# ComparatorSense.net
KiCad netlist of a schematic drawn in Altium Designer
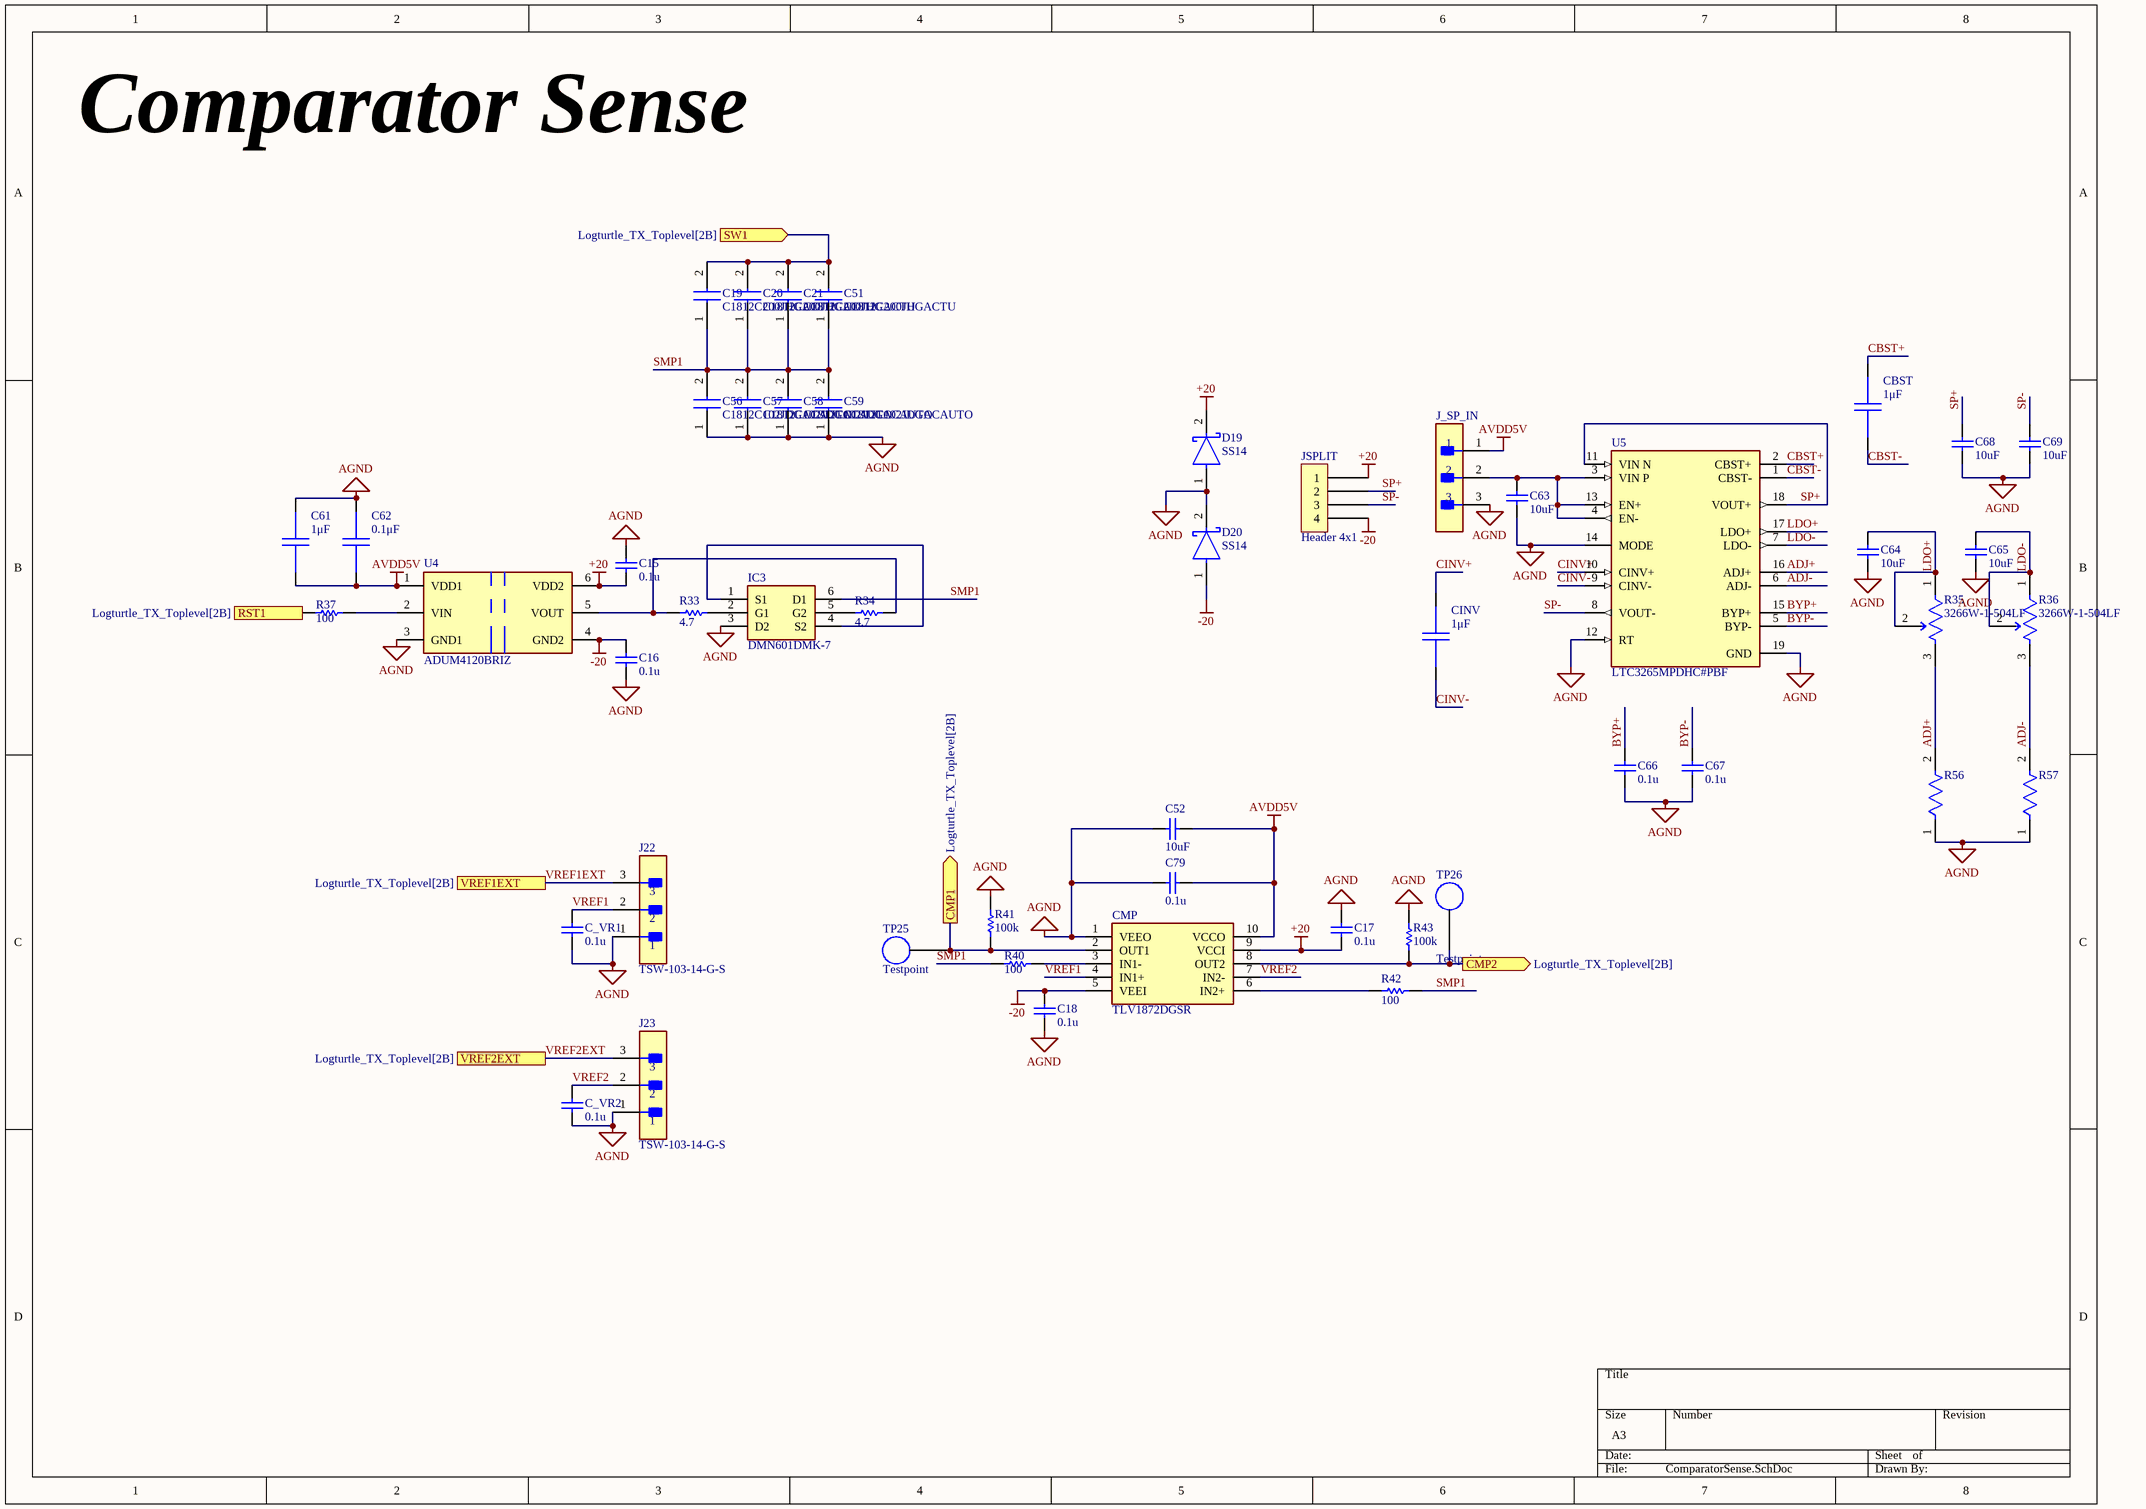
[diagram p0: ComparatorSense.SchDoc]

(export (version "E")
  (design (tool "Eeschema 10.0.6"))
  (components
    (comp (ref "C15")
      (value "0.1u")
      (footprint "CAPC1608X09N")
      (description "Capacitor")
      (libsource (lib "LOGTURTLE_APR_25_TX") (part "Capacitor"))
    )
    (comp (ref "C16")
      (value "0.1u")
      (footprint "CAPC1608X09N")
      (description "Capacitor")
      (libsource (lib "LOGTURTLE_APR_25_TX") (part "Capacitor"))
    )
    (comp (ref "C17")
      (value "0.1u")
      (footprint "CAPC1608X09N")
      (description "Capacitor")
      (libsource (lib "LOGTURTLE_APR_25_TX") (part "Capacitor"))
    )
    (comp (ref "C18")
      (value "0.1u")
      (footprint "CAPC1608X09N")
      (description "Capacitor")
      (libsource (lib "LOGTURTLE_APR_25_TX") (part "Capacitor"))
    )
    (comp (ref "C19")
      (value "C1812C200JHGACTU")
      (footprint "C1812")
      (description "Capacitor")
      (fields (field (name "MANUFACTURER_PART_NUMBER") "C1812C102JDGACAUTO"))
      (libsource (lib "LOGTURTLE_APR_25_TX") (part "C1812C102JDGACAUTO"))
    )
    (comp (ref "C20")
      (value "C1812C200JHGACTU")
      (footprint "C1812")
      (description "Capacitor")
      (fields (field (name "MANUFACTURER_PART_NUMBER") "C1812C102JDGACAUTO"))
      (libsource (lib "LOGTURTLE_APR_25_TX") (part "C1812C102JDGACAUTO"))
    )
    (comp (ref "C21")
      (value "C1812C200JHGACTU")
      (footprint "C1812")
      (description "Capacitor")
      (fields (field (name "MANUFACTURER_PART_NUMBER") "C1812C102JDGACAUTO"))
      (libsource (lib "LOGTURTLE_APR_25_TX") (part "C1812C102JDGACAUTO"))
    )
    (comp (ref "C51")
      (value "C1812C200JHGACTU")
      (footprint "C1812")
      (description "Capacitor")
      (fields (field (name "MANUFACTURER_PART_NUMBER") "C1812C102JDGACAUTO"))
      (libsource (lib "LOGTURTLE_APR_25_TX") (part "C1812C102JDGACAUTO"))
    )
    (comp (ref "C52")
      (value "10uF")
      (footprint "CAPC2012X14N")
      (fields
        (field (name "MANUFACTURER") "Murata")
        (field (name "MANUFACTURER PART NUMBER") "GRM21BZ71E106KE15L")
        (field (name "TOLERANCE") "10%")
      )
      (libsource (lib "LOGTURTLE_APR_25_TX") (part "GRM21BZ71E106KE15L"))
    )
    (comp (ref "C56")
      (value "C1812C102JDGACAUTO")
      (footprint "C1812")
      (description "Capacitor")
      (libsource (lib "LOGTURTLE_APR_25_TX") (part "C1812C102JDGACAUTO"))
    )
    (comp (ref "C57")
      (value "C1812C102JDGACAUTO")
      (footprint "C1812")
      (description "Capacitor")
      (libsource (lib "LOGTURTLE_APR_25_TX") (part "C1812C102JDGACAUTO"))
    )
    (comp (ref "C58")
      (value "C1812C102JDGACAUTO")
      (footprint "C1812")
      (description "Capacitor")
      (libsource (lib "LOGTURTLE_APR_25_TX") (part "C1812C102JDGACAUTO"))
    )
    (comp (ref "C59")
      (value "C1812C102JDGACAUTO")
      (footprint "C1812")
      (description "Capacitor")
      (libsource (lib "LOGTURTLE_APR_25_TX") (part "C1812C102JDGACAUTO"))
    )
    (comp (ref "C61")
      (value "1μF")
      (footprint "CAPC1608X09N")
      (fields
        (field (name "MANUFACTURER") "Yageo")
        (field (name "MANUFACTURER PART NUMBER") "CC0603KRX7R7BB105")
      )
      (libsource (lib "LOGTURTLE_APR_25_TX") (part "CC0603KRX7R7BB105"))
    )
    (comp (ref "C62")
      (value "0.1μF")
      (footprint "CAPC1608X90N")
      (fields
        (field (name "MANUFACTURER") "Yageo")
        (field (name "MANUFACTURER PART NUMBER") "CC0603KRX7R7BB104")
      )
      (libsource (lib "LOGTURTLE_APR_25_TX") (part "CC0603KRX7R7BB104"))
    )
    (comp (ref "C63")
      (value "10uF")
      (footprint "CAPC2012X14N")
      (fields
        (field (name "MANUFACTURER") "Murata")
        (field (name "MANUFACTURER PART NUMBER") "GRM21BZ71E106KE15L")
        (field (name "TOLERANCE") "10%")
      )
      (libsource (lib "LOGTURTLE_APR_25_TX") (part "GRM21BZ71E106KE15L"))
    )
    (comp (ref "C64")
      (value "10uF")
      (footprint "CAPC2012X14N")
      (fields
        (field (name "MANUFACTURER") "Murata")
        (field (name "MANUFACTURER PART NUMBER") "GRM21BZ71E106KE15L")
        (field (name "TOLERANCE") "10%")
      )
      (libsource (lib "LOGTURTLE_APR_25_TX") (part "GRM21BZ71E106KE15L"))
    )
    (comp (ref "C65")
      (value "10uF")
      (footprint "CAPC2012X14N")
      (fields
        (field (name "MANUFACTURER") "Murata")
        (field (name "MANUFACTURER PART NUMBER") "GRM21BZ71E106KE15L")
        (field (name "TOLERANCE") "10%")
      )
      (libsource (lib "LOGTURTLE_APR_25_TX") (part "GRM21BZ71E106KE15L"))
    )
    (comp (ref "C66")
      (value "0.1u")
      (footprint "CAPC1608X09N")
      (description "Capacitor")
      (libsource (lib "LOGTURTLE_APR_25_TX") (part "Capacitor"))
    )
    (comp (ref "C67")
      (value "0.1u")
      (footprint "CAPC1608X09N")
      (description "Capacitor")
      (libsource (lib "LOGTURTLE_APR_25_TX") (part "Capacitor"))
    )
    (comp (ref "C68")
      (value "10uF")
      (footprint "CAPC2012X14N")
      (fields
        (field (name "MANUFACTURER") "Murata")
        (field (name "MANUFACTURER PART NUMBER") "GRM21BZ71E106KE15L")
        (field (name "TOLERANCE") "10%")
      )
      (libsource (lib "LOGTURTLE_APR_25_TX") (part "GRM21BZ71E106KE15L"))
    )
    (comp (ref "C69")
      (value "10uF")
      (footprint "CAPC2012X14N")
      (fields
        (field (name "MANUFACTURER") "Murata")
        (field (name "MANUFACTURER PART NUMBER") "GRM21BZ71E106KE15L")
        (field (name "TOLERANCE") "10%")
      )
      (libsource (lib "LOGTURTLE_APR_25_TX") (part "GRM21BZ71E106KE15L"))
    )
    (comp (ref "C79")
      (value "0.1u")
      (footprint "CAPC1608X09N")
      (description "Capacitor")
      (libsource (lib "LOGTURTLE_APR_25_TX") (part "Capacitor"))
    )
    (comp (ref "CBST")
      (value "1μF")
      (footprint "CAPC1608X09N")
      (fields
        (field (name "MANUFACTURER") "Yageo")
        (field (name "MANUFACTURER PART NUMBER") "CC0603KRX7R7BB105")
      )
      (libsource (lib "LOGTURTLE_APR_25_TX") (part "CC0603KRX7R7BB105"))
    )
    (comp (ref "CINV")
      (value "1μF")
      (footprint "CAPC1608X09N")
      (fields
        (field (name "MANUFACTURER") "Yageo")
        (field (name "MANUFACTURER PART NUMBER") "CC0603KRX7R7BB105")
      )
      (libsource (lib "LOGTURTLE_APR_25_TX") (part "CC0603KRX7R7BB105"))
    )
    (comp (ref "CMP")
      (value "TLV1872DGSR")
      (footprint "SOP50P490X110-10N")
      (description "Integrated Circuit")
      (fields (field (name "MOUSER PART NUMBER") "595-TLV1872DGSR"))
      (libsource (lib "Logturtle_Power_Transmitter") (part "TLV1872DGSR"))
    )
    (comp (ref "C_VR1")
      (value "0.1u")
      (footprint "CAPC1608X09N")
      (description "Capacitor")
      (libsource (lib "LOGTURTLE_APR_25_TX") (part "Capacitor"))
    )
    (comp (ref "C_VR2")
      (value "0.1u")
      (footprint "CAPC1608X09N")
      (description "Capacitor")
      (libsource (lib "LOGTURTLE_APR_25_TX") (part "Capacitor"))
    )
    (comp (ref "D19")
      (value "SS14")
      (footprint "FP-403AE-MFG")
      (description "DIODE SCHOTTKY 40V 1A SMA")
      (fields
        (field (name "MANUFACTURER") "ON Semiconductor")
        (field (name "OCTOPART") "https://octopart.com/ss14-on+semiconductor-29205033")
      )
      (libsource (lib "Altium Content Vault") (part "360ad2f4ac25a952324d13796385471"))
    )
    (comp (ref "D20")
      (value "SS14")
      (footprint "FP-403AE-MFG")
      (description "DIODE SCHOTTKY 40V 1A SMA")
      (fields
        (field (name "MANUFACTURER") "ON Semiconductor")
        (field (name "OCTOPART") "https://octopart.com/ss14-on+semiconductor-29205033")
      )
      (libsource (lib "Altium Content Vault") (part "360ad2f4ac25a952324d13796385471"))
    )
    (comp (ref "IC3")
      (value "DMN601DMK-7")
      (footprint "LOGTURTLE_APR_25_TX:SOT95P285X140-6N")
      (description "MOSFET (N-Channel)")
      (fields (field (name "MOUSER PART NUMBER") "621-DMN601DMK-7"))
      (libsource (lib "LOGTURTLE_APR_25_TX") (part "DMN601DMK-7"))
    )
    (comp (ref "J22")
      (value "TSW-103-14-G-S")
      (footprint "FP-TSW-103-14-G-S-MFG")
      (description "CONN HEADER VERT 3POS 2.54MM")
      (libsource (lib "") (part "cd3439d6ef35ae5d9b27ec4fdd3e828_1"))
    )
    (comp (ref "J23")
      (value "TSW-103-14-G-S")
      (footprint "FP-TSW-103-14-G-S-MFG")
      (description "CONN HEADER VERT 3POS 2.54MM")
      (libsource (lib "") (part "cd3439d6ef35ae5d9b27ec4fdd3e828_1"))
    )
    (comp (ref "JSPLIT")
      (value "Header 4x1")
      (footprint "HDRV4W64P0X254_1X4_1016X250X901P")
      (libsource (lib "LOGTURTLE_APR_25_TX") (part "Header 4x1"))
    )
    (comp (ref "J_SP_IN")
      (value "TSW-103-14-G-S")
      (footprint "FP-TSW-103-14-G-S-MFG")
      (description "CONN HEADER VERT 3POS 2.54MM")
      (libsource (lib "Altium Content Vault") (part "cd3439d6ef35ae5d9b27ec4fdd3e828"))
    )
    (comp (ref "R33")
      (value "4.7")
      (footprint "RESC1608X55N")
      (description "Resistor, 100 Ohms ±1% 0.1W, 1/10W Chip Resistor 0603 (1608 Metric) Moisture Resistant Thick Film")
      (fields
        (field (name "MANUFACTURER_PART_NUMBER") "RC0603FR-07100RL")
        (field (name "MOUSER PART NUMBER") "603-RC0603FR-07100RL")
      )
      (libsource (lib "LOGTURTLE_APR_25_TX") (part "RC0603FR-07100RL"))
    )
    (comp (ref "R34")
      (value "4.7")
      (footprint "RESC1608X55N")
      (description "Resistor, 100 Ohms ±1% 0.1W, 1/10W Chip Resistor 0603 (1608 Metric) Moisture Resistant Thick Film")
      (fields
        (field (name "MANUFACTURER_PART_NUMBER") "RC0603FR-07100RL")
        (field (name "MOUSER PART NUMBER") "603-RC0603FR-07100RL")
      )
      (libsource (lib "LOGTURTLE_APR_25_TX") (part "RC0603FR-07100RL"))
    )
    (comp (ref "R35")
      (value "3266W-1-504LF")
      (footprint "FP-3266W-MFG")
      (description "TRIMMER 500KOHM 0.25W PC PIN TOP")
      (fields (field (name "TOLERANCE") "10%"))
      (libsource (lib "Altium Content Vault") (part "2dcfd2547301a7d3209a5e99acfd772"))
    )
    (comp (ref "R36")
      (value "3266W-1-504LF")
      (footprint "FP-3266W-MFG")
      (description "TRIMMER 500KOHM 0.25W PC PIN TOP")
      (fields (field (name "TOLERANCE") "10%"))
      (libsource (lib "Altium Content Vault") (part "2dcfd2547301a7d3209a5e99acfd772"))
    )
    (comp (ref "R37")
      (value "100")
      (footprint "RESC1608X55N")
      (description "Resistor, 100 Ohms ±1% 0.1W, 1/10W Chip Resistor 0603 (1608 Metric) Moisture Resistant Thick Film")
      (fields
        (field (name "MANUFACTURER_PART_NUMBER") "RC0603FR-07100RL")
        (field (name "MOUSER PART NUMBER") "603-RC0603FR-07100RL")
      )
      (libsource (lib "LOGTURTLE_APR_25_TX") (part "RC0603FR-07100RL"))
    )
    (comp (ref "R40")
      (value "100")
      (footprint "RESC1608X55N")
      (description "Resistor, 100 Ohms ±1% 0.1W, 1/10W Chip Resistor 0603 (1608 Metric) Moisture Resistant Thick Film")
      (fields
        (field (name "MANUFACTURER_PART_NUMBER") "RC0603FR-07100RL")
        (field (name "MOUSER PART NUMBER") "603-RC0603FR-07100RL")
      )
      (libsource (lib "LOGTURTLE_APR_25_TX") (part "RC0603FR-07100RL"))
    )
    (comp (ref "R41")
      (value "100k")
      (footprint "RESC1608X55N")
      (description "Resistor, 100 kOhms ±1% 0.1W, 1/10W Chip Resistor 0603 (1608 Metric) Moisture Resistant Thick Film")
      (fields
        (field (name "MANUFACTURER_PART_NUMBER") "RC0603FR-07100KL")
        (field (name "MOUSER PART NUMBER") "603-RC0603FR-07100KL")
      )
      (libsource (lib "LOGTURTLE_APR_25_TX") (part "RC0603FR-07100KL"))
    )
    (comp (ref "R42")
      (value "100")
      (footprint "RESC1608X55N")
      (description "Resistor, 100 Ohms ±1% 0.1W, 1/10W Chip Resistor 0603 (1608 Metric) Moisture Resistant Thick Film")
      (fields
        (field (name "MANUFACTURER_PART_NUMBER") "RC0603FR-07100RL")
        (field (name "MOUSER PART NUMBER") "603-RC0603FR-07100RL")
      )
      (libsource (lib "LOGTURTLE_APR_25_TX") (part "RC0603FR-07100RL"))
    )
    (comp (ref "R43")
      (value "100k")
      (footprint "RESC1608X55N")
      (description "Resistor, 100 kOhms ±1% 0.1W, 1/10W Chip Resistor 0603 (1608 Metric) Moisture Resistant Thick Film")
      (fields
        (field (name "MANUFACTURER_PART_NUMBER") "RC0603FR-07100KL")
        (field (name "MOUSER PART NUMBER") "603-RC0603FR-07100KL")
      )
      (libsource (lib "LOGTURTLE_APR_25_TX") (part "RC0603FR-07100KL"))
    )
    (comp (ref "R56")
      (value "TNPU060350K0HZEN00")
      (footprint "FP-TNPU0603-e3-MFG")
      (description "RES SMD 50K OHM 0.02% 1/10W 0603")
      (fields (field (name "TOLERANCE") "0.02%"))
      (libsource (lib "Altium Content Vault") (part "1029c3af85768c4190bb7ad29bc67b5"))
    )
    (comp (ref "R57")
      (value "TNPU060350K0HZEN00")
      (footprint "FP-TNPU0603-e3-MFG")
      (description "RES SMD 50K OHM 0.02% 1/10W 0603")
      (fields (field (name "TOLERANCE") "0.02%"))
      (libsource (lib "Altium Content Vault") (part "1029c3af85768c4190bb7ad29bc67b5"))
    )
    (comp (ref "TP25")
      (value "Testpoint")
      (footprint "TP_5006")
      (libsource (lib "LOGTURTLE_APR_25_TX") (part "Testpoint"))
    )
    (comp (ref "TP26")
      (value "Testpoint")
      (footprint "TP_5006")
      (libsource (lib "LOGTURTLE_APR_25_TX") (part "Testpoint"))
    )
    (comp (ref "U4")
      (value "ADUM4120BRIZ")
      (footprint "FP-RI-6-1-IPC_A")
      (description "DGTL ISO 5KV 1CH GATE DRVR 6SOIC")
      (libsource (lib "Altium Content Vault") (part "e55926c47189122d5b09d9f2327802d"))
    )
    (comp (ref "U5")
      (value "LTC3265MPDHC#PBF")
      (footprint "FP-DHC-18-05-08-1955-IPC_C")
      (description "IC REG CHARGE PUMP INV 18DFN")
      (libsource (lib "Altium Content Vault") (part "3b4ba725209a09f593a7c32de91ac41"))
    )
  )
  (nets
    (net (code "1") (name "+20") (class "Default")
      (node (ref "C15") (pin "2") (pinfunction "2_2") (pintype "passive"))
      (node (ref "C17") (pin "2") (pinfunction "2_2") (pintype "passive"))
      (node (ref "CMP") (pin "9") (pinfunction "VCCI_9") (pintype "passive"))
      (node (ref "D19") (pin "2") (pinfunction "C_2") (pintype "passive"))
      (node (ref "JSPLIT") (pin "1") (pinfunction "1_1") (pintype "passive"))
      (node (ref "U4") (pin "6") (pinfunction "VDD2_6") (pintype "power_in"))
    )
    (net (code "2") (name "-20") (class "Default")
      (node (ref "C16") (pin "2") (pinfunction "2_2") (pintype "passive"))
      (node (ref "C18") (pin "2") (pinfunction "2_2") (pintype "passive"))
      (node (ref "CMP") (pin "5") (pinfunction "VEEI_5") (pintype "passive"))
      (node (ref "D20") (pin "1") (pinfunction "A_1") (pintype "passive"))
      (node (ref "JSPLIT") (pin "4") (pinfunction "4_4") (pintype "passive"))
      (node (ref "U4") (pin "4") (pinfunction "GND2_4") (pintype "power_in"))
    )
    (net (code "3") (name "/ADJ+") (class "Default")
      (node (ref "R35") (pin "3") (pinfunction "CW_3") (pintype "passive"))
      (node (ref "R56") (pin "2") (pinfunction "2_2") (pintype "passive"))
      (node (ref "U5") (pin "16") (pinfunction "ADJ+_16") (pintype "passive"))
    )
    (net (code "4") (name "/ADJ-") (class "Default")
      (node (ref "R36") (pin "3") (pinfunction "CW_3") (pintype "passive"))
      (node (ref "R57") (pin "2") (pinfunction "2_2") (pintype "passive"))
      (node (ref "U5") (pin "6") (pinfunction "ADJ-_6") (pintype "passive"))
    )
    (net (code "5") (name "/BYP+") (class "Default")
      (node (ref "C66") (pin "1") (pinfunction "1_1") (pintype "passive"))
      (node (ref "U5") (pin "15") (pinfunction "BYP+_15") (pintype "passive"))
    )
    (net (code "6") (name "/BYP-") (class "Default")
      (node (ref "C67") (pin "1") (pinfunction "1_1") (pintype "passive"))
      (node (ref "U5") (pin "5") (pinfunction "BYP-_5") (pintype "passive"))
    )
    (net (code "7") (name "/CBST+") (class "Default")
      (node (ref "CBST") (pin "1") (pinfunction "1_1") (pintype "passive"))
      (node (ref "U5") (pin "2") (pinfunction "CBST+_2") (pintype "passive"))
    )
    (net (code "8") (name "/CBST-") (class "Default")
      (node (ref "CBST") (pin "2") (pinfunction "2_2") (pintype "passive"))
      (node (ref "U5") (pin "1") (pinfunction "CBST-_1") (pintype "passive"))
    )
    (net (code "9") (name "/CINV+") (class "Default")
      (node (ref "CINV") (pin "1") (pinfunction "1_1") (pintype "passive"))
      (node (ref "U5") (pin "10") (pinfunction "CINV+_10") (pintype "input"))
    )
    (net (code "10") (name "/CINV-") (class "Default")
      (node (ref "CINV") (pin "2") (pinfunction "2_2") (pintype "passive"))
      (node (ref "U5") (pin "9") (pinfunction "CINV-_9") (pintype "input"))
    )
    (net (code "11") (name "/CMP1") (class "Default")
      (node (ref "CMP") (pin "2") (pinfunction "OUT1_2") (pintype "passive"))
      (node (ref "R41") (pin "2") (pinfunction "2_2") (pintype "passive"))
      (node (ref "TP25") (pin "1") (pinfunction "1_1") (pintype "passive"))
    )
    (net (code "12") (name "/CMP2") (class "Default")
      (node (ref "CMP") (pin "8") (pinfunction "OUT2_8") (pintype "passive"))
      (node (ref "R43") (pin "2") (pinfunction "2_2") (pintype "passive"))
      (node (ref "TP26") (pin "1") (pinfunction "1_1") (pintype "passive"))
    )
    (net (code "13") (name "/LDO+") (class "Default")
      (node (ref "C64") (pin "2") (pinfunction "2_2") (pintype "passive"))
      (node (ref "R35") (pin "1") (pinfunction "CCW_1") (pintype "passive"))
      (node (ref "R35") (pin "2") (pinfunction "WIPER_2") (pintype "passive"))
      (node (ref "U5") (pin "17") (pinfunction "LDO+_17") (pintype "output"))
    )
    (net (code "14") (name "/LDO-") (class "Default")
      (node (ref "C65") (pin "2") (pinfunction "2_2") (pintype "passive"))
      (node (ref "R36") (pin "1") (pinfunction "CCW_1") (pintype "passive"))
      (node (ref "R36") (pin "2") (pinfunction "WIPER_2") (pintype "passive"))
      (node (ref "U5") (pin "7") (pinfunction "LDO-_7") (pintype "output"))
    )
    (net (code "15") (name "/RST1") (class "Default")
      (node (ref "R37") (pin "1") (pinfunction "1_1") (pintype "passive"))
    )
    (net (code "16") (name "/SMP1") (class "Default")
      (node (ref "C19") (pin "1") (pinfunction "1_1") (pintype "passive"))
      (node (ref "C20") (pin "1") (pinfunction "1_1") (pintype "passive"))
      (node (ref "C21") (pin "1") (pinfunction "1_1") (pintype "passive"))
      (node (ref "C51") (pin "1") (pinfunction "1_1") (pintype "passive"))
      (node (ref "C56") (pin "2") (pinfunction "2_2") (pintype "passive"))
      (node (ref "C57") (pin "2") (pinfunction "2_2") (pintype "passive"))
      (node (ref "C58") (pin "2") (pinfunction "2_2") (pintype "passive"))
      (node (ref "C59") (pin "2") (pinfunction "2_2") (pintype "passive"))
      (node (ref "IC3") (pin "6") (pinfunction "D1_6") (pintype "passive"))
      (node (ref "R40") (pin "1") (pinfunction "1_1") (pintype "passive"))
      (node (ref "R42") (pin "1") (pinfunction "1_1") (pintype "passive"))
    )
    (net (code "17") (name "/SP+") (class "Default")
      (node (ref "C68") (pin "2") (pinfunction "2_2") (pintype "passive"))
      (node (ref "JSPLIT") (pin "2") (pinfunction "2_2") (pintype "passive"))
      (node (ref "U5") (pin "11") (pinfunction "VIN_N_11") (pintype "input"))
      (node (ref "U5") (pin "18") (pinfunction "VOUT+_18") (pintype "output"))
    )
    (net (code "18") (name "/SP-") (class "Default")
      (node (ref "C69") (pin "2") (pinfunction "2_2") (pintype "passive"))
      (node (ref "JSPLIT") (pin "3") (pinfunction "3_3") (pintype "passive"))
      (node (ref "U5") (pin "8") (pinfunction "VOUT-_8") (pintype "output"))
    )
    (net (code "19") (name "/SW1") (class "Default")
      (node (ref "C19") (pin "2") (pinfunction "2_2") (pintype "passive"))
      (node (ref "C20") (pin "2") (pinfunction "2_2") (pintype "passive"))
      (node (ref "C21") (pin "2") (pinfunction "2_2") (pintype "passive"))
      (node (ref "C51") (pin "2") (pinfunction "2_2") (pintype "passive"))
    )
    (net (code "20") (name "/VREF1") (class "Default")
      (node (ref "CMP") (pin "4") (pinfunction "IN1+_4") (pintype "passive"))
      (node (ref "C_VR1") (pin "2") (pinfunction "2_2") (pintype "passive"))
      (node (ref "J22") (pin "2") (pinfunction "2_2") (pintype "passive"))
    )
    (net (code "21") (name "/VREF1EXT") (class "Default")
      (node (ref "J22") (pin "3") (pinfunction "3_3") (pintype "passive"))
    )
    (net (code "22") (name "/VREF2") (class "Default")
      (node (ref "CMP") (pin "7") (pinfunction "IN2-_7") (pintype "passive"))
      (node (ref "C_VR2") (pin "2") (pinfunction "2_2") (pintype "passive"))
      (node (ref "J23") (pin "2") (pinfunction "2_2") (pintype "passive"))
    )
    (net (code "23") (name "/VREF2EXT") (class "Default")
      (node (ref "J23") (pin "3") (pinfunction "3_3") (pintype "passive"))
    )
    (net (code "24") (name "AGND") (class "Default")
      (node (ref "C15") (pin "1") (pinfunction "1_1") (pintype "passive"))
      (node (ref "C16") (pin "1") (pinfunction "1_1") (pintype "passive"))
      (node (ref "C17") (pin "1") (pinfunction "1_1") (pintype "passive"))
      (node (ref "C18") (pin "1") (pinfunction "1_1") (pintype "passive"))
      (node (ref "C52") (pin "1") (pinfunction "1_1") (pintype "passive"))
      (node (ref "C56") (pin "1") (pinfunction "1_1") (pintype "passive"))
      (node (ref "C57") (pin "1") (pinfunction "1_1") (pintype "passive"))
      (node (ref "C58") (pin "1") (pinfunction "1_1") (pintype "passive"))
      (node (ref "C59") (pin "1") (pinfunction "1_1") (pintype "passive"))
      (node (ref "C61") (pin "1") (pinfunction "1_1") (pintype "passive"))
      (node (ref "C62") (pin "1") (pinfunction "1_1") (pintype "passive"))
      (node (ref "C63") (pin "1") (pinfunction "1_1") (pintype "passive"))
      (node (ref "C64") (pin "1") (pinfunction "1_1") (pintype "passive"))
      (node (ref "C65") (pin "1") (pinfunction "1_1") (pintype "passive"))
      (node (ref "C66") (pin "2") (pinfunction "2_2") (pintype "passive"))
      (node (ref "C67") (pin "2") (pinfunction "2_2") (pintype "passive"))
      (node (ref "C68") (pin "1") (pinfunction "1_1") (pintype "passive"))
      (node (ref "C69") (pin "1") (pinfunction "1_1") (pintype "passive"))
      (node (ref "C79") (pin "2") (pinfunction "2_2") (pintype "passive"))
      (node (ref "CMP") (pin "1") (pinfunction "VEEO_1") (pintype "passive"))
      (node (ref "C_VR1") (pin "1") (pinfunction "1_1") (pintype "passive"))
      (node (ref "C_VR2") (pin "1") (pinfunction "1_1") (pintype "passive"))
      (node (ref "D19") (pin "1") (pinfunction "A_1") (pintype "passive"))
      (node (ref "D20") (pin "2") (pinfunction "C_2") (pintype "passive"))
      (node (ref "IC3") (pin "3") (pinfunction "D2_3") (pintype "passive"))
      (node (ref "J22") (pin "1") (pinfunction "1_1") (pintype "passive"))
      (node (ref "J23") (pin "1") (pinfunction "1_1") (pintype "passive"))
      (node (ref "J_SP_IN") (pin "3") (pinfunction "3_3") (pintype "passive"))
      (node (ref "R41") (pin "1") (pinfunction "1_1") (pintype "passive"))
      (node (ref "R43") (pin "1") (pinfunction "1_1") (pintype "passive"))
      (node (ref "R56") (pin "1") (pinfunction "1_1") (pintype "passive"))
      (node (ref "R57") (pin "1") (pinfunction "1_1") (pintype "passive"))
      (node (ref "U4") (pin "3") (pinfunction "GND1_3") (pintype "power_in"))
      (node (ref "U5") (pin "12") (pinfunction "RT_12") (pintype "input"))
      (node (ref "U5") (pin "14") (pinfunction "MODE_14") (pintype "passive"))
      (node (ref "U5") (pin "19") (pinfunction "GND_19") (pintype "power_in"))
    )
    (net (code "25") (name "AVDD5V") (class "Default")
      (node (ref "C52") (pin "2") (pinfunction "2_2") (pintype "passive"))
      (node (ref "C61") (pin "2") (pinfunction "2_2") (pintype "passive"))
      (node (ref "C62") (pin "2") (pinfunction "2_2") (pintype "passive"))
      (node (ref "C79") (pin "1") (pinfunction "1_1") (pintype "passive"))
      (node (ref "CMP") (pin "10") (pinfunction "VCCO_10") (pintype "passive"))
      (node (ref "J_SP_IN") (pin "1") (pinfunction "1_1") (pintype "passive"))
      (node (ref "U4") (pin "1") (pinfunction "VDD1_1") (pintype "power_in"))
    )
    (net (code "26") (name "Net-(CMP-IN1-)") (class "Default")
      (node (ref "CMP") (pin "3") (pinfunction "IN1-_3") (pintype "passive"))
      (node (ref "R40") (pin "2") (pinfunction "2_2") (pintype "passive"))
    )
    (net (code "27") (name "Net-(CMP-IN2+)") (class "Default")
      (node (ref "CMP") (pin "6") (pinfunction "IN2+_6") (pintype "passive"))
      (node (ref "R42") (pin "2") (pinfunction "2_2") (pintype "passive"))
    )
    (net (code "28") (name "Net-(IC3-G1)") (class "Default")
      (node (ref "IC3") (pin "2") (pinfunction "G1_2") (pintype "passive"))
      (node (ref "R33") (pin "1") (pinfunction "1_1") (pintype "passive"))
    )
    (net (code "29") (name "Net-(IC3-G2)") (class "Default")
      (node (ref "IC3") (pin "5") (pinfunction "G2_5") (pintype "passive"))
      (node (ref "R34") (pin "2") (pinfunction "2_2") (pintype "passive"))
    )
    (net (code "30") (name "Net-(IC3-S1)") (class "Default")
      (node (ref "IC3") (pin "1") (pinfunction "S1_1") (pintype "passive"))
      (node (ref "IC3") (pin "4") (pinfunction "S2_4") (pintype "passive"))
    )
    (net (code "31") (name "Net-(U4-VIN)") (class "Default")
      (node (ref "R37") (pin "2") (pinfunction "2_2") (pintype "passive"))
      (node (ref "U4") (pin "2") (pinfunction "VIN_2") (pintype "power_in"))
    )
    (net (code "32") (name "Net-(U4-VOUT)") (class "Default")
      (node (ref "R33") (pin "2") (pinfunction "2_2") (pintype "passive"))
      (node (ref "R34") (pin "1") (pinfunction "1_1") (pintype "passive"))
      (node (ref "U4") (pin "5") (pinfunction "VOUT_5") (pintype "power_in"))
    )
    (net (code "33") (name "Net-(U5-EN+)") (class "Default")
      (node (ref "C63") (pin "2") (pinfunction "2_2") (pintype "passive"))
      (node (ref "J_SP_IN") (pin "2") (pinfunction "2_2") (pintype "passive"))
      (node (ref "U5") (pin "13") (pinfunction "EN+_13") (pintype "input"))
      (node (ref "U5") (pin "3") (pinfunction "VIN_P_3") (pintype "input"))
      (node (ref "U5") (pin "4") (pinfunction "EN-_4") (pintype "output"))
    )
  )
)
